# Connectors.net
KiCad netlist of a schematic drawn in Altium Designer
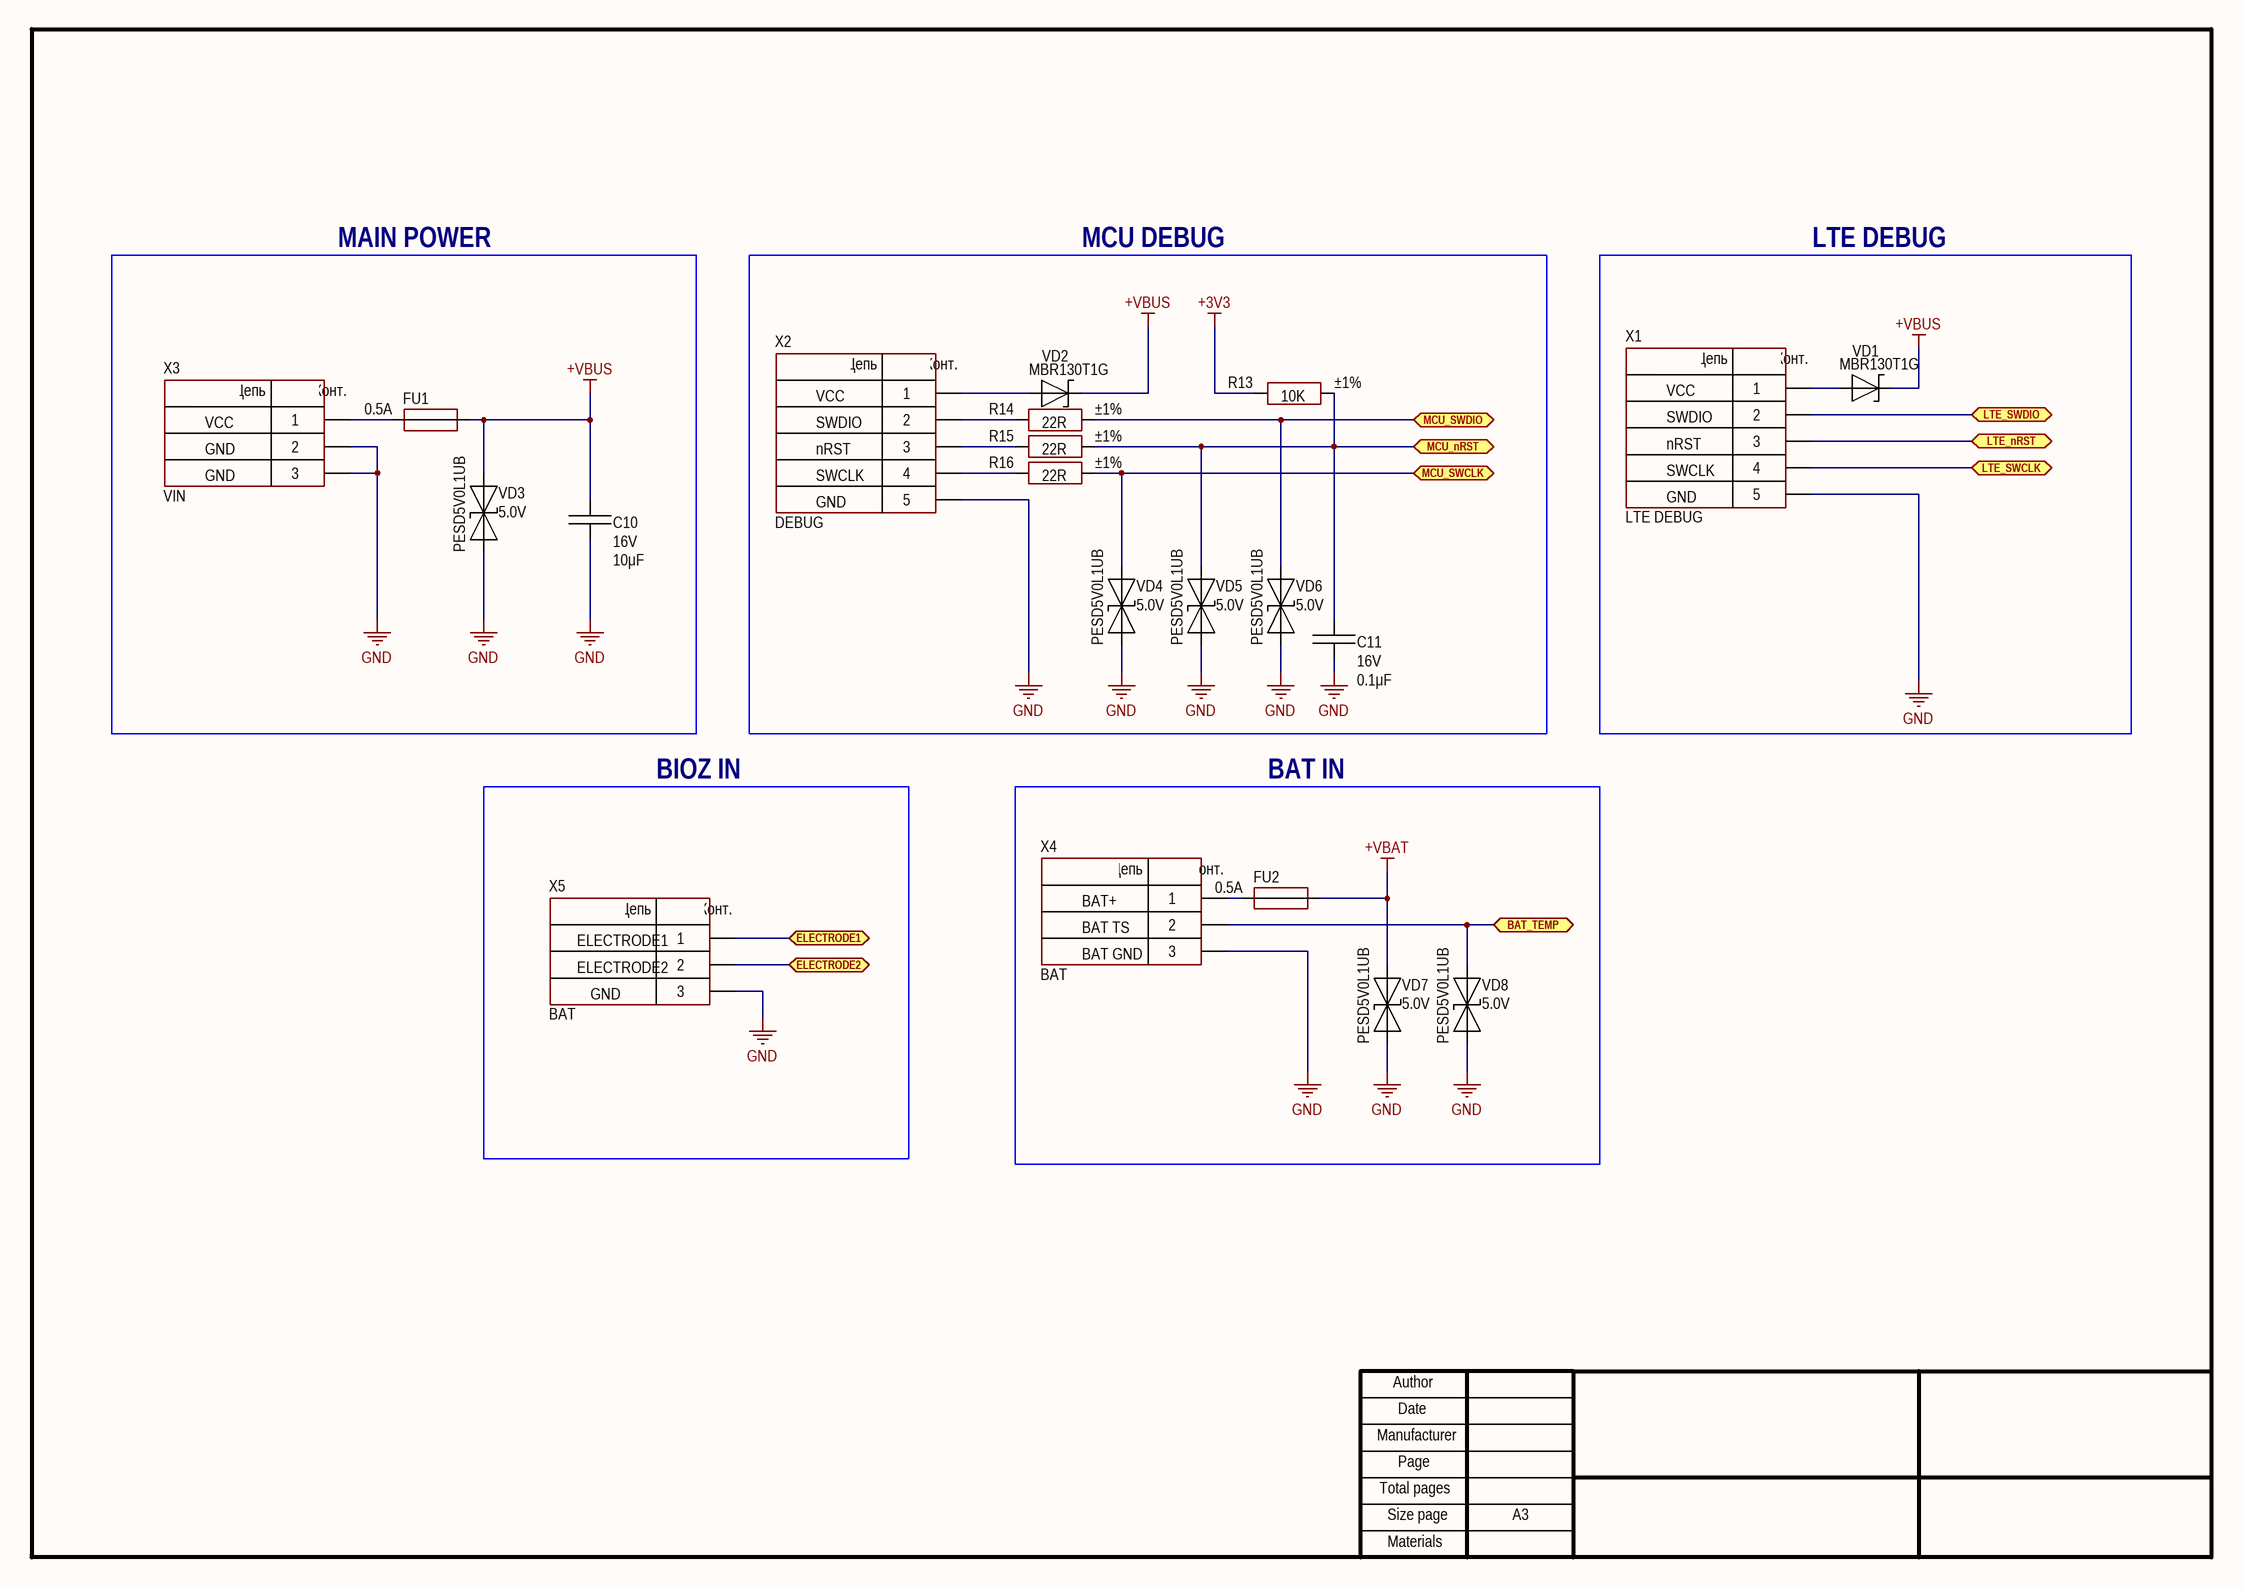
[diagram p0: Connectors.SchDoc]

(export (version "E")
  (design (tool "Eeschema 10.0.6"))
  (components
    (comp (ref "C10")
      (value "10μF")
      (footprint "CAP: 0805")
      (description "10 µF ±20% 16V Ceramic Capacitor X7R 0805 (2012 Metric)")
      (fields
        (field (name "MANUFACTURER") "Yageo")
        (field (name "PARTNUMBER") "CC0805MKX7R7BB106")
        (field (name "VOLTAGE") "16V")
      )
      (libsource (lib "capacitor") (part "Ceramic_0805"))
    )
    (comp (ref "C11")
      (value "0.1μF")
      (footprint "CAP: 0805")
      (fields
        (field (name "MANUFACTURER") "Yageo")
        (field (name "PARTNUMBER") "CC0805KRX7R7BB104")
        (field (name "VALUEMANUFACTURERPARTNUMBER") "Ceramic capacitor, 0.1μF, X7R, ±10%, 16V, 0805, -55...+125°C")
        (field (name "VOLTAGE") "16V")
      )
      (libsource (lib "capacitor") (part "Ceramic_0805"))
    )
    (comp (ref "FU1")
      (value "~")
      (footprint "FUSE: 1206")
      (description "Polymeric PTC Resettable Fuse 6V 500 mA Ih Surface Mount 0805 (2012 Metric), Concave")
      (fields
        (field (name "MANUFACTURER") "Bel Fuse")
        (field (name "VALUEMANUFACTURERPARTNUMBER") "Electromechanics relay, 250VAC, 0.5A, 1206, ")
        (field (name "MAXCURRENT") "0.5A")
      )
      (libsource (lib "electromechanics") (part "Fuse"))
    )
    (comp (ref "FU2")
      (value "~")
      (footprint "FUSE: 1206")
      (description "Polymeric PTC Resettable Fuse 6V 500 mA Ih Surface Mount 0805 (2012 Metric), Concave")
      (fields
        (field (name "MANUFACTURER") "Bel Fuse")
        (field (name "VALUEMANUFACTURERPARTNUMBER") "Electromechanics relay, 250VAC, 0.5A, 1206, ")
        (field (name "MAXCURRENT") "0.5A")
      )
      (libsource (lib "electromechanics") (part "Fuse"))
    )
    (comp (ref "R13")
      (value "10K")
      (footprint "RES: 0805")
      (description "10 kOhms ±1% 0.125W, 1/8W Chip Resistor 0805 (2012 Metric) Moisture Resistant Thick Film")
      (fields
        (field (name "MANUFACTURER") "Yageo")
        (field (name "PARTNUMBER") "RC0805FR-0710KL")
        (field (name "TOLERANCE") "±1%")
      )
      (libsource (lib "resistor") (part "Resistor_0805"))
    )
    (comp (ref "R14")
      (value "22R")
      (footprint "RES: 0805")
      (description "22 Ohms ±1% 0.125W, 1/8W Chip Resistor 0805 (2012 Metric) Moisture Resistant Thick Film")
      (fields
        (field (name "MANUFACTURER") "Yageo")
        (field (name "PARTNUMBER") "RC0805FR-0722RL")
        (field (name "TOLERANCE") "±1%")
      )
      (libsource (lib "resistor") (part "Resistor_0805"))
    )
    (comp (ref "R15")
      (value "22R")
      (footprint "RES: 0805")
      (description "22 Ohms ±1% 0.125W, 1/8W Chip Resistor 0805 (2012 Metric) Moisture Resistant Thick Film")
      (fields
        (field (name "MANUFACTURER") "Yageo")
        (field (name "PARTNUMBER") "RC0805FR-0722RL")
        (field (name "TOLERANCE") "±1%")
      )
      (libsource (lib "resistor") (part "Resistor_0805"))
    )
    (comp (ref "R16")
      (value "22R")
      (footprint "RES: 0805")
      (description "22 Ohms ±1% 0.125W, 1/8W Chip Resistor 0805 (2012 Metric) Moisture Resistant Thick Film")
      (fields
        (field (name "MANUFACTURER") "Yageo")
        (field (name "PARTNUMBER") "RC0805FR-0722RL")
        (field (name "TOLERANCE") "±1%")
      )
      (libsource (lib "resistor") (part "Resistor_0805"))
    )
    (comp (ref "VD1")
      (value "~")
      (footprint "DIODE: SOD123")
      (description "Diode Schottky 30 V 1A Surface Mount SOD-123")
      (fields
        (field (name "MANUFACTURER") "Diodes Incorporated")
        (field (name "VALUEMANUFACTURERPARTNUMBER") "Schottky diode, 30V, 1A, 0.45V, 15pF, SOD-123, -55...+150°C")
        (field (name "PARTNUMBER") "MBR130T1G")
      )
      (libsource (lib "diode") (part "Schottky_single"))
    )
    (comp (ref "VD2")
      (value "~")
      (footprint "DIODE: SOD123")
      (description "Diode Schottky 30 V 1A Surface Mount SOD-123")
      (fields
        (field (name "MANUFACTURER") "Diodes Incorporated")
        (field (name "VALUEMANUFACTURERPARTNUMBER") "Schottky diode, 30V, 1A, 0.45V, 15pF, SOD-123, -55...+150°C")
        (field (name "PARTNUMBER") "MBR130T1G")
      )
      (libsource (lib "diode") (part "Schottky_single"))
    )
    (comp (ref "VD3")
      (value "~")
      (footprint "DIODE: SOD523")
      (description "12V Clamp 3.5A (8/20µs) Ipp Tvs Diode Surface Mount SOD-523")
      (fields
        (field (name "MANUFACTURER") "Nexperia")
        (field (name "VALUEMANUFACTURERPARTNUMBER") "ESD TVS diode, 5.0V, 3.5A, , , SOD-523, -55...+150°C")
        (field (name "VOLTAGE") "5.0V")
        (field (name "PARTNUMBER") "PESD5V0L1UB")
      )
      (libsource (lib "diode") (part "TVS_single"))
    )
    (comp (ref "VD4")
      (value "~")
      (footprint "DIODE: SOD523")
      (description "12V Clamp 3.5A (8/20µs) Ipp Tvs Diode Surface Mount SOD-523")
      (fields
        (field (name "MANUFACTURER") "Nexperia")
        (field (name "VALUEMANUFACTURERPARTNUMBER") "ESD TVS diode, 5.0V, 3.5A, , , SOD-523, -55...+150°C")
        (field (name "VOLTAGE") "5.0V")
        (field (name "PARTNUMBER") "PESD5V0L1UB")
      )
      (libsource (lib "diode") (part "TVS_single"))
    )
    (comp (ref "VD5")
      (value "~")
      (footprint "DIODE: SOD523")
      (description "12V Clamp 3.5A (8/20µs) Ipp Tvs Diode Surface Mount SOD-523")
      (fields
        (field (name "MANUFACTURER") "Nexperia")
        (field (name "VALUEMANUFACTURERPARTNUMBER") "ESD TVS diode, 5.0V, 3.5A, , , SOD-523, -55...+150°C")
        (field (name "VOLTAGE") "5.0V")
        (field (name "PARTNUMBER") "PESD5V0L1UB")
      )
      (libsource (lib "diode") (part "TVS_single"))
    )
    (comp (ref "VD6")
      (value "~")
      (footprint "DIODE: SOD523")
      (description "12V Clamp 3.5A (8/20µs) Ipp Tvs Diode Surface Mount SOD-523")
      (fields
        (field (name "MANUFACTURER") "Nexperia")
        (field (name "VALUEMANUFACTURERPARTNUMBER") "ESD TVS diode, 5.0V, 3.5A, , , SOD-523, -55...+150°C")
        (field (name "VOLTAGE") "5.0V")
        (field (name "PARTNUMBER") "PESD5V0L1UB")
      )
      (libsource (lib "diode") (part "TVS_single"))
    )
    (comp (ref "VD7")
      (value "~")
      (footprint "DIODE: SOD523")
      (description "12V Clamp 3.5A (8/20µs) Ipp Tvs Diode Surface Mount SOD-523")
      (fields
        (field (name "MANUFACTURER") "Nexperia")
        (field (name "VALUEMANUFACTURERPARTNUMBER") "ESD TVS diode, 5.0V, 3.5A, , , SOD-523, -55...+150°C")
        (field (name "VOLTAGE") "5.0V")
        (field (name "PARTNUMBER") "PESD5V0L1UB")
      )
      (libsource (lib "diode") (part "TVS_single"))
    )
    (comp (ref "VD8")
      (value "~")
      (footprint "DIODE: SOD523")
      (description "12V Clamp 3.5A (8/20µs) Ipp Tvs Diode Surface Mount SOD-523")
      (fields
        (field (name "MANUFACTURER") "Nexperia")
        (field (name "VALUEMANUFACTURERPARTNUMBER") "ESD TVS diode, 5.0V, 3.5A, , , SOD-523, -55...+150°C")
        (field (name "VOLTAGE") "5.0V")
        (field (name "PARTNUMBER") "PESD5V0L1UB")
      )
      (libsource (lib "diode") (part "TVS_single"))
    )
    (comp (ref "X1")
      (value "~")
      (footprint "CON: PLS-5")
      (fields
        (field (name "MANUFACTURER") "Connfly")
        (field (name "VALUEMANUFACTURERPARTNUMBER") "Connector, 5pin, 2.54mm, 500VAC, 3A")
        (field (name "PARTNUMBER") "PLS-5")
        (field (name "COMMENTTEXT") "LTE DEBUG")
      )
      (libsource (lib "connector") (part "PLS-5"))
    )
    (comp (ref "X2")
      (value "~")
      (footprint "CON: PLS-5")
      (description "Connector Header Through Hole 5 position 0.100\" (2.54mm)")
      (fields
        (field (name "MANUFACTURER") "Würth Elektronik")
        (field (name "VALUEMANUFACTURERPARTNUMBER") "Connector, 5pin, 2.54mm, 500VAC, 3A")
        (field (name "COMMENTTEXT") "DEBUG")
      )
      (libsource (lib "connector") (part "PLS-5"))
    )
    (comp (ref "X3")
      (value "~")
      (footprint "CON: DG350-3.5-03P")
      (description "3 Position Wire to Board Terminal Block Horizontal with Board 0.138\" (3.50mm) Through Hole")
      (fields
        (field (name "MANUFACTURER") "TE Connectivity")
        (field (name "VALUEMANUFACTURERPARTNUMBER") "Terminal connector, 3pin, 3.5mm, 300VAC, 12A")
        (field (name "COMMENTTEXT") "VIN")
      )
      (libsource (lib "connector") (part "Connector_terminal_3pin"))
    )
    (comp (ref "X4")
      (value "~")
      (footprint "CON: DG350-3.5-03P")
      (description "3 Position Wire to Board Terminal Block Horizontal with Board 0.138\" (3.50mm) Through Hole")
      (fields
        (field (name "MANUFACTURER") "TE Connectivity")
        (field (name "VALUEMANUFACTURERPARTNUMBER") "Terminal connector, 3pin, 3.5mm, 300VAC, 12A")
        (field (name "COMMENTTEXT") "BAT")
      )
      (libsource (lib "connector") (part "Connector_terminal_3pin"))
    )
    (comp (ref "X5")
      (value "~")
      (footprint "CON: DG350-3.5-03P")
      (description "3 Position Wire to Board Terminal Block Horizontal with Board 0.138\" (3.50mm) Through Hole")
      (fields
        (field (name "MANUFACTURER") "TE Connectivity")
        (field (name "VALUEMANUFACTURERPARTNUMBER") "Terminal connector, 3pin, 3.5mm, 300VAC, 12A")
        (field (name "COMMENTTEXT") "BAT")
      )
      (libsource (lib "connector") (part "Connector_terminal_3pin"))
    )
  )
  (nets
    (net (code "1") (name "+3V3") (class "Default")
      (node (ref "R13") (pin "1") (pinfunction "1_1") (pintype "passive"))
    )
    (net (code "2") (name "+VBAT") (class "Default")
      (node (ref "FU2") (pin "2") (pinfunction "2_2") (pintype "passive"))
      (node (ref "VD7") (pin "2") (pinfunction "C_2") (pintype "passive"))
    )
    (net (code "3") (name "+VBUS") (class "Default")
      (node (ref "C10") (pin "2") (pinfunction "2_2") (pintype "passive"))
      (node (ref "FU1") (pin "2") (pinfunction "2_2") (pintype "passive"))
      (node (ref "VD1") (pin "2") (pinfunction "2_2") (pintype "passive"))
      (node (ref "VD2") (pin "2") (pinfunction "2_2") (pintype "passive"))
      (node (ref "VD3") (pin "2") (pinfunction "C_2") (pintype "passive"))
    )
    (net (code "4") (name "/BAT_TEMP") (class "Default")
      (node (ref "VD8") (pin "2") (pinfunction "C_2") (pintype "passive"))
      (node (ref "X4") (pin "2") (pinfunction "2_2") (pintype "passive"))
    )
    (net (code "5") (name "/ELECTRODE1") (class "Default")
      (node (ref "X5") (pin "1") (pinfunction "1_1") (pintype "passive"))
    )
    (net (code "6") (name "/ELECTRODE2") (class "Default")
      (node (ref "X5") (pin "2") (pinfunction "2_2") (pintype "passive"))
    )
    (net (code "7") (name "/LTE_SWCLK") (class "Default")
      (node (ref "X1") (pin "4") (pinfunction "4_4") (pintype "power_in"))
    )
    (net (code "8") (name "/LTE_SWDIO") (class "Default")
      (node (ref "X1") (pin "2") (pinfunction "2_2") (pintype "passive"))
    )
    (net (code "9") (name "/LTE_nRST") (class "Default")
      (node (ref "X1") (pin "3") (pinfunction "3_3") (pintype "power_in"))
    )
    (net (code "10") (name "/MCU_SWCLK") (class "Default")
      (node (ref "R16") (pin "2") (pinfunction "2_2") (pintype "passive"))
      (node (ref "VD4") (pin "2") (pinfunction "C_2") (pintype "passive"))
    )
    (net (code "11") (name "/MCU_SWDIO") (class "Default")
      (node (ref "R14") (pin "2") (pinfunction "2_2") (pintype "passive"))
      (node (ref "VD6") (pin "2") (pinfunction "C_2") (pintype "passive"))
    )
    (net (code "12") (name "/MCU_nRST") (class "Default")
      (node (ref "C11") (pin "2") (pinfunction "2_2") (pintype "passive"))
      (node (ref "R13") (pin "2") (pinfunction "2_2") (pintype "passive"))
      (node (ref "R15") (pin "2") (pinfunction "2_2") (pintype "passive"))
      (node (ref "VD5") (pin "2") (pinfunction "C_2") (pintype "passive"))
    )
    (net (code "13") (name "GND") (class "Default")
      (node (ref "C10") (pin "1") (pinfunction "1_1") (pintype "passive"))
      (node (ref "C11") (pin "1") (pinfunction "1_1") (pintype "passive"))
      (node (ref "VD3") (pin "1") (pinfunction "A_1") (pintype "passive"))
      (node (ref "VD4") (pin "1") (pinfunction "A_1") (pintype "passive"))
      (node (ref "VD5") (pin "1") (pinfunction "A_1") (pintype "passive"))
      (node (ref "VD6") (pin "1") (pinfunction "A_1") (pintype "passive"))
      (node (ref "VD7") (pin "1") (pinfunction "A_1") (pintype "passive"))
      (node (ref "VD8") (pin "1") (pinfunction "A_1") (pintype "passive"))
      (node (ref "X1") (pin "5") (pinfunction "5_5") (pintype "power_in"))
      (node (ref "X2") (pin "5") (pinfunction "5_5") (pintype "power_in"))
      (node (ref "X3") (pin "2") (pinfunction "2_2") (pintype "passive"))
      (node (ref "X3") (pin "3") (pinfunction "3_3") (pintype "power_in"))
      (node (ref "X4") (pin "3") (pinfunction "3_3") (pintype "power_in"))
      (node (ref "X5") (pin "3") (pinfunction "3_3") (pintype "power_in"))
    )
    (net (code "14") (name "Net-(FU1-Pad1)") (class "Default")
      (node (ref "FU1") (pin "1") (pinfunction "1_1") (pintype "passive"))
      (node (ref "X3") (pin "1") (pinfunction "1_1") (pintype "passive"))
    )
    (net (code "15") (name "Net-(FU2-Pad1)") (class "Default")
      (node (ref "FU2") (pin "1") (pinfunction "1_1") (pintype "passive"))
      (node (ref "X4") (pin "1") (pinfunction "1_1") (pintype "passive"))
    )
    (net (code "16") (name "Net-(R14-Pad1)") (class "Default")
      (node (ref "R14") (pin "1") (pinfunction "1_1") (pintype "passive"))
      (node (ref "X2") (pin "2") (pinfunction "2_2") (pintype "passive"))
    )
    (net (code "17") (name "Net-(R15-Pad1)") (class "Default")
      (node (ref "R15") (pin "1") (pinfunction "1_1") (pintype "passive"))
      (node (ref "X2") (pin "3") (pinfunction "3_3") (pintype "power_in"))
    )
    (net (code "18") (name "Net-(R16-Pad1)") (class "Default")
      (node (ref "R16") (pin "1") (pinfunction "1_1") (pintype "passive"))
      (node (ref "X2") (pin "4") (pinfunction "4_4") (pintype "power_in"))
    )
    (net (code "19") (name "Net-(VD1-Pad1)") (class "Default")
      (node (ref "VD1") (pin "1") (pinfunction "1_1") (pintype "passive"))
      (node (ref "X1") (pin "1") (pinfunction "1_1") (pintype "passive"))
    )
    (net (code "20") (name "Net-(VD2-Pad1)") (class "Default")
      (node (ref "VD2") (pin "1") (pinfunction "1_1") (pintype "passive"))
      (node (ref "X2") (pin "1") (pinfunction "1_1") (pintype "passive"))
    )
  )
)
